# TwoDigitThermometer.net
KiCad netlist of a schematic drawn in EAGLE
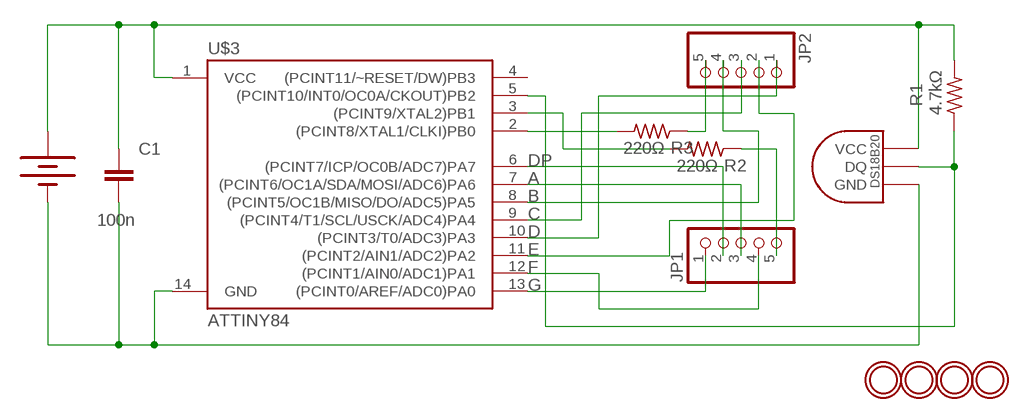
[diagram p0: schematic, sheet 1]

(export (version "E")
  (design (tool "Eeschema 10.0.6"))
  (components
    (comp (ref "BAT1")
      (value "20mm coincell")
      (footprint "eagle-import:BATTCON_20MM")
      (libsource (lib "eagle-import") (part "BATTERY20SMD"))
    )
    (comp (ref "C1")
      (value "100n")
      (footprint "eagle-import:0603-CAP")
      (libsource (lib "eagle-import") (part "CAP0603-CAP"))
    )
    (comp (ref "JP1")
      (value "HEADER-1X5EDGESMT")
      (footprint "eagle-import:1X05_EDGESMT")
      (libsource (lib "eagle-import") (part "HEADER-1X5EDGESMT"))
    )
    (comp (ref "JP2")
      (value "HEADER-1X5EDGESMT")
      (footprint "eagle-import:1X05_EDGESMT")
      (libsource (lib "eagle-import") (part "HEADER-1X5EDGESMT"))
    )
    (comp (ref "R1")
      (value "4.7kΩ")
      (footprint "eagle-import:R0805")
      (libsource (lib "eagle-import") (part "R-US_R0805"))
    )
    (comp (ref "R2")
      (value "220Ω")
      (footprint "eagle-import:R0805")
      (libsource (lib "eagle-import") (part "R-US_R0805"))
    )
    (comp (ref "R3")
      (value "220Ω")
      (footprint "eagle-import:R0805")
      (libsource (lib "eagle-import") (part "R-US_R0805"))
    )
    (comp (ref "U$1")
      (value "MOUNTINGHOLE2.5")
      (footprint "eagle-import:MOUNTINGHOLE_2.5_PLATED")
      (libsource (lib "eagle-import") (part "MOUNTINGHOLE2.5"))
    )
    (comp (ref "U$2")
      (value "DS1820")
      (footprint "eagle-import:µSOP8")
      (libsource (lib "eagle-import") (part "DS1820"))
    )
    (comp (ref "U$3")
      (value "ATTINY84")
      (footprint "eagle-import:SO14")
      (libsource (lib "eagle-import") (part "ATTINY84"))
    )
    (comp (ref "U$4")
      (value "MOUNTINGHOLE2.5")
      (footprint "eagle-import:MOUNTINGHOLE_2.5_PLATED")
      (libsource (lib "eagle-import") (part "MOUNTINGHOLE2.5"))
    )
    (comp (ref "U$5")
      (value "MOUNTINGHOLE2.5")
      (footprint "eagle-import:MOUNTINGHOLE_2.5_PLATED")
      (libsource (lib "eagle-import") (part "MOUNTINGHOLE2.5"))
    )
    (comp (ref "U$9")
      (value "MOUNTINGHOLE2.5")
      (footprint "eagle-import:MOUNTINGHOLE_2.5_PLATED")
      (libsource (lib "eagle-import") (part "MOUNTINGHOLE2.5"))
    )
  )
  (nets
    (net (code "1") (name "A") (class "Default")
      (node (ref "JP1") (pin "3") (pinfunction "3_3") (pintype "passive"))
      (node (ref "U$3") (pin "7") (pinfunction "(PCINT6/OC1A/SDA/MOSI/ADC6)PA6_7") (pintype "bidirectional"))
    )
    (net (code "2") (name "B") (class "Default")
      (node (ref "JP2") (pin "4") (pinfunction "4_4") (pintype "passive"))
      (node (ref "U$3") (pin "8") (pinfunction "(PCINT5/OC1B/MISO/DO/ADC5)PA5_8") (pintype "bidirectional"))
    )
    (net (code "3") (name "C") (class "Default")
      (node (ref "JP2") (pin "3") (pinfunction "3_3") (pintype "passive"))
      (node (ref "U$3") (pin "9") (pinfunction "(PCINT4/T1/SCL/USCK/ADC4)PA4_9") (pintype "bidirectional"))
    )
    (net (code "4") (name "D") (class "Default")
      (node (ref "JP2") (pin "1") (pinfunction "1_1") (pintype "passive"))
      (node (ref "U$3") (pin "10") (pinfunction "(PCINT3/T0/ADC3)PA3_10") (pintype "bidirectional"))
    )
    (net (code "5") (name "DP") (class "Default")
      (node (ref "JP1") (pin "2") (pinfunction "2_2") (pintype "passive"))
      (node (ref "U$3") (pin "6") (pinfunction "(PCINT7/ICP/OC0B/ADC7)PA7_6") (pintype "bidirectional"))
    )
    (net (code "6") (name "E") (class "Default")
      (node (ref "JP2") (pin "2") (pinfunction "2_2") (pintype "passive"))
      (node (ref "U$3") (pin "11") (pinfunction "(PCINT2/AIN1/ADC2)PA2_11") (pintype "bidirectional"))
    )
    (net (code "7") (name "F") (class "Default")
      (node (ref "JP1") (pin "4") (pinfunction "4_4") (pintype "passive"))
      (node (ref "U$3") (pin "12") (pinfunction "(PCINT1/AIN0/ADC1)PA1_12") (pintype "bidirectional"))
    )
    (net (code "8") (name "G") (class "Default")
      (node (ref "JP1") (pin "1") (pinfunction "1_1") (pintype "passive"))
      (node (ref "U$3") (pin "13") (pinfunction "(PCINT0/AREF/ADC0)PA0_13") (pintype "bidirectional"))
    )
    (net (code "9") (name "Net-(BAT1-+)") (class "Default")
      (node (ref "BAT1") (pin "1") (pinfunction "+_1") (pintype "power_in"))
      (node (ref "C1") (pin "1") (pinfunction "1_1") (pintype "passive"))
      (node (ref "R1") (pin "2") (pinfunction "2_2") (pintype "passive"))
      (node (ref "U$2") (pin "8") (pinfunction "VCC_8") (pintype "power_in"))
      (node (ref "U$3") (pin "1") (pinfunction "VCC_1") (pintype "bidirectional"))
    )
    (net (code "10") (name "Net-(BAT1--)") (class "Default")
      (node (ref "BAT1") (pin "2") (pinfunction "-_2") (pintype "power_in"))
      (node (ref "C1") (pin "2") (pinfunction "2_2") (pintype "passive"))
      (node (ref "U$2") (pin "4") (pinfunction "GND_4") (pintype "power_in"))
      (node (ref "U$3") (pin "14") (pinfunction "GND_14") (pintype "bidirectional"))
    )
    (net (code "11") (name "Net-(JP1-Pad5)") (class "Default")
      (node (ref "JP1") (pin "5") (pinfunction "5_5") (pintype "passive"))
      (node (ref "R2") (pin "1") (pinfunction "1_1") (pintype "passive"))
    )
    (net (code "12") (name "Net-(JP2-Pad5)") (class "Default")
      (node (ref "JP2") (pin "5") (pinfunction "5_5") (pintype "passive"))
      (node (ref "R3") (pin "1") (pinfunction "1_1") (pintype "passive"))
    )
    (net (code "13") (name "Net-(U$2-DQ)") (class "Default")
      (node (ref "R1") (pin "1") (pinfunction "1_1") (pintype "passive"))
      (node (ref "U$2") (pin "1") (pinfunction "DQ_1") (pintype "bidirectional"))
      (node (ref "U$3") (pin "5") (pinfunction "(PCINT10/INT0/OC0A/CKOUT)PB2_5") (pintype "bidirectional"))
    )
    (net (code "14") (name "Net-(U$3-(PCINT8{slash}XTAL1{slash}CLKI)PB0)") (class "Default")
      (node (ref "R3") (pin "2") (pinfunction "2_2") (pintype "passive"))
      (node (ref "U$3") (pin "2") (pinfunction "(PCINT8/XTAL1/CLKI)PB0_2") (pintype "bidirectional"))
    )
    (net (code "15") (name "Net-(U$3-(PCINT9{slash}XTAL2)PB1)") (class "Default")
      (node (ref "R2") (pin "2") (pinfunction "2_2") (pintype "passive"))
      (node (ref "U$3") (pin "3") (pinfunction "(PCINT9/XTAL2)PB1_3") (pintype "bidirectional"))
    )
    (net (code "16") (name "unconnected-(U$3-(PCINT11{slash}~{RESET{slash}DW})PB3-Pad4)") (class "Default")
      (node (ref "U$3") (pin "4") (pinfunction "(PCINT11/~{RESET/DW})PB3_4") (pintype "bidirectional"))
    )
  )
)
